# LTEMSubsystem.net
KiCad netlist of a schematic drawn in Altium Designer
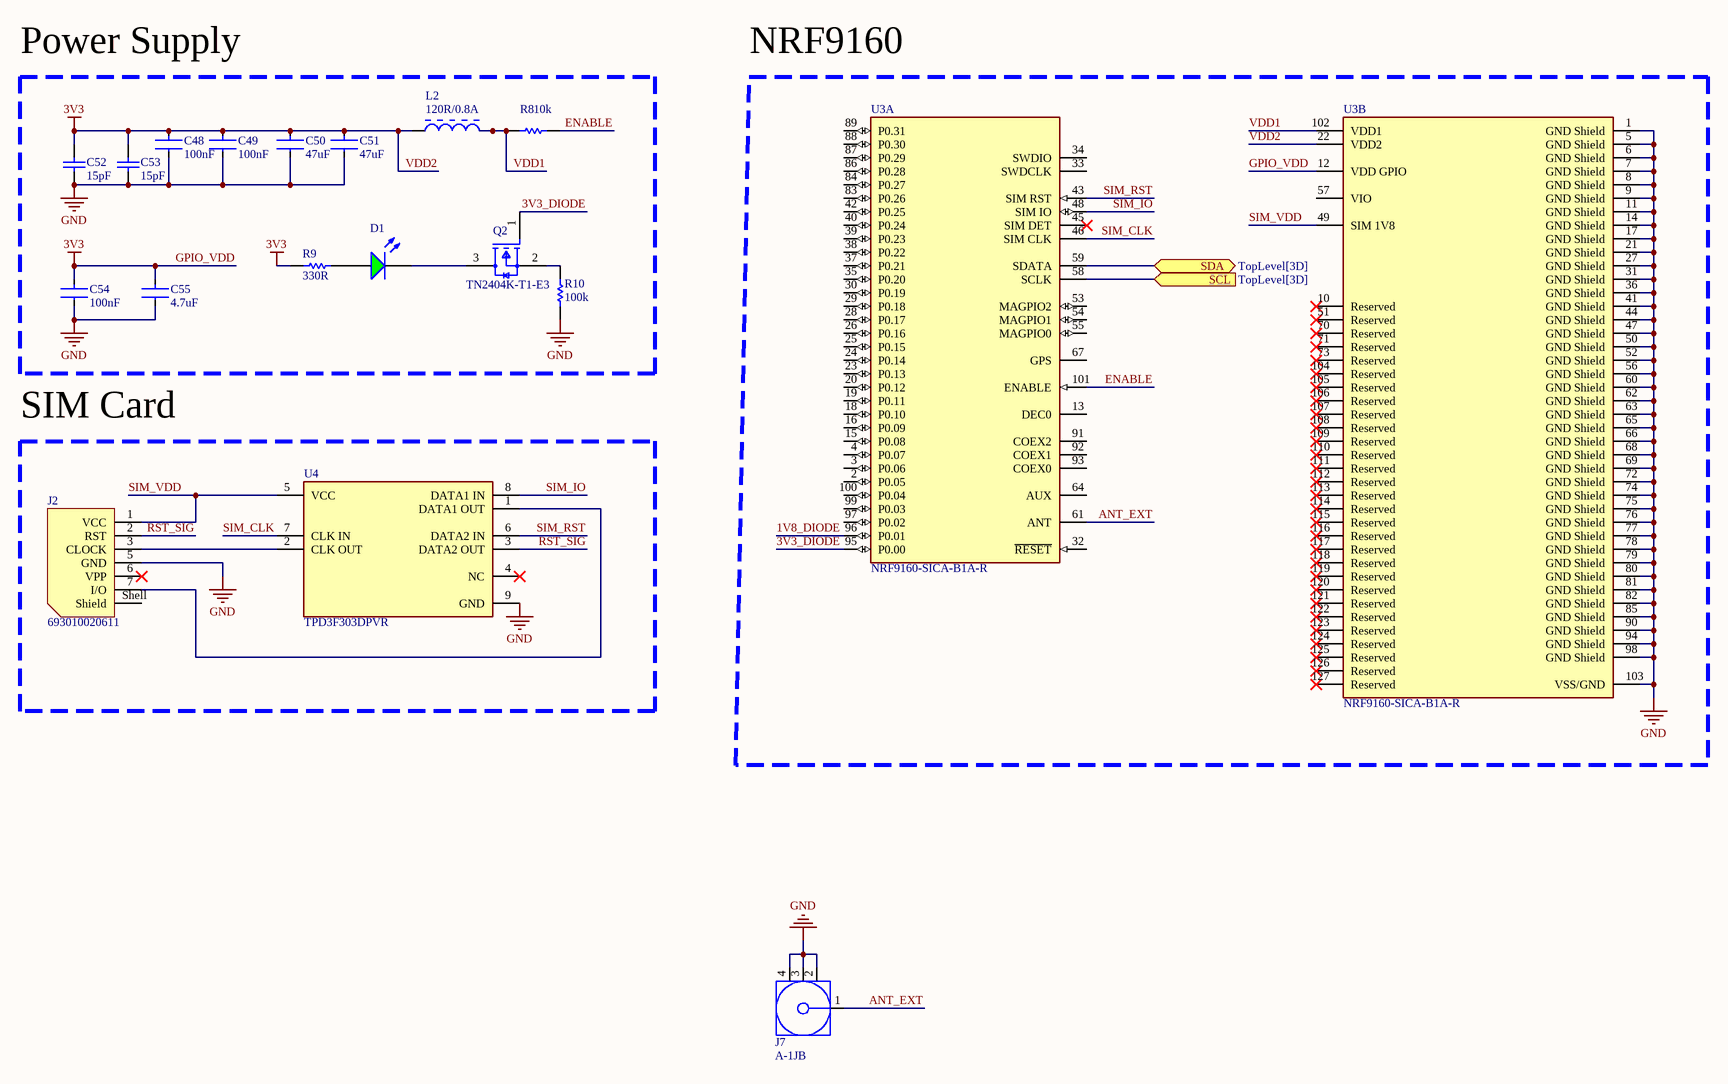
[diagram p0: LTEMSubsystem.SchDoc]

(export (version "E")
  (design (tool "Eeschema 10.0.6"))
  (components
    (comp (ref "C48")
      (value "100nF")
      (footprint "FP-GRM033-0_03-MFG")
      (description "GRM033R60J104KE19D")
      (fields (field (name "VOLTAGE") "6.3V") (field (name "TOLERANCE") "10%"))
      (libsource (lib "Altium Content Vault") (part "b4654b650e69147ec39a6b967a45e02"))
    )
    (comp (ref "C49")
      (value "100nF")
      (footprint "FP-GRM033-0_03-MFG")
      (description "GRM033R60J104KE19D")
      (fields (field (name "VOLTAGE") "6.3V") (field (name "TOLERANCE") "10%"))
      (libsource (lib "Altium Content Vault") (part "b4654b650e69147ec39a6b967a45e02"))
    )
    (comp (ref "C50")
      (value "47uF")
      (footprint "FP-C3216-160-0_2-MFG")
      (description "C3216X5R1C476M160AB")
      (fields (field (name "TOLERANCE") "20%"))
      (libsource (lib "Altium Content Vault") (part "11868f565c42a9108669ba33697ecf6"))
    )
    (comp (ref "C51")
      (value "47uF")
      (footprint "FP-C3216-160-0_2-MFG")
      (description "C3216X5R1C476M160AB")
      (fields (field (name "TOLERANCE") "20%"))
      (libsource (lib "Altium Content Vault") (part "11868f565c42a9108669ba33697ecf6"))
    )
    (comp (ref "C52")
      (value "15pF")
      (footprint "CAPC1508X91X25LL25T13")
      (description "06032U150GAT2A")
      (fields (field (name "MANUFACTURER") "AVX Interconnect / Elco"))
      (libsource (lib "Altium Content Vault") (part "CAP"))
    )
    (comp (ref "C53")
      (value "15pF")
      (footprint "CAPC1508X91X25LL25T13")
      (description "06032U150GAT2A")
      (fields (field (name "MANUFACTURER") "AVX Interconnect / Elco"))
      (libsource (lib "Altium Content Vault") (part "CAP"))
    )
    (comp (ref "C54")
      (value "100nF")
      (footprint "FP-GRM033-0_03-MFG")
      (description "GRM033R60J104KE19D")
      (fields (field (name "VOLTAGE") "6.3V") (field (name "TOLERANCE") "10%"))
      (libsource (lib "Altium Content Vault") (part "b4654b650e69147ec39a6b967a45e02"))
    )
    (comp (ref "C55")
      (value "4.7uF")
      (footprint "FP-C0603-CG-MFG")
      (description "C0603C475K9PACTU")
      (fields (field (name "TOLERANCE") "10%") (field (name "MANUFACTURER") "Kemet"))
      (libsource (lib "Altium Content Vault") (part "11868f565c42a9108669ba33697ecf6"))
    )
    (comp (ref "D1")
      (value "~")
      (footprint "WL-SMRW_1206_cylindrical_reverse use")
      (description "156120GS75300")
      (libsource (lib "Altium Content Vault") (part "LED_Green_2A-1K"))
    )
    (comp (ref "J2")
      (value "693010020611")
      (footprint "693010020611")
      (libsource (lib "Altium Content Vault") (part "693010020611"))
    )
    (comp (ref "J7")
      (value "A-1JB")
      (footprint "AMPH-A-1JB_V")
      (description "AMC PCB Jack, 0 to 60 GHz, 60 V, -40 to 90 degC, 4-Pin SMD, RoHS, Tape and Reel")
      (fields (field (name "TOLERANCE") "10%"))
      (libsource (lib "Altium Content Vault") (part "CN-S-3F-RF4"))
    )
    (comp (ref "L2")
      (value "120R/0.8A")
      (footprint "LIRD-LI0805H151R-10-2_V")
      (description "LI0805H121R-10")
      (fields (field (name "MANUFACTURER") "Laird"))
      (libsource (lib "Altium Content Vault") (part "IND-FB-2"))
    )
    (comp (ref "Q2")
      (value "TN2404K-T1-E3")
      (footprint "FP-S-03946-MFG")
      (description "TN2404K-T1-E3 Single N-Channel 240 V 4 Ohms Surface Mount Power Mosfet - SOT-23")
      (libsource (lib "Altium Content Vault") (part "0a9ea7c96deaaede766a5b531c28de0"))
    )
    (comp (ref "R8")
      (value "10k")
      (footprint "RESC1609X50X30NL8T20")
      (description "CRCW060310K0FKEA")
      (fields (field (name "MANUFACTURER") "Vishay Semiconductor"))
      (libsource (lib "Altium Content Vault") (part "RES-2"))
    )
    (comp (ref "R9")
      (value "330R")
      (footprint "RESC1005X40X25ML05T05")
      (description "ERJ2RKF3300X")
      (fields (field (name "MANUFACTURER") "Panasonic"))
      (libsource (lib "Altium Content Vault") (part "RES"))
    )
    (comp (ref "R10")
      (value "100k")
      (footprint "RESC1005X40X25NL10T10")
      (description "ERA-2AED104X")
      (fields (field (name "MANUFACTURER") "Panasonic"))
      (libsource (lib "Altium Content Vault") (part "RES"))
    )
    (comp (ref "U3")
      (value "NRF9160-SICA-B1A-R")
      (footprint "FP-NRF9160-SICA-B1A-R-MFG")
      (description "NRF9160-SICA-B1A-R LTE-M/NB-IoT/GPS Module 700MHz to 2200MHz 3.3V to 5.5V LGA")
      (libsource (lib "") (part "a84498b94899327ece239e71cba79b0_1"))
    )
    (comp (ref "U4")
      (value "TPD3F303DPVR")
      (footprint "FP-DPV0008A-IPC_C")
      (description "FILTER RC(PI) ESD SMD")
      (libsource (lib "Altium Content Vault") (part "1bc37876499b18a7cf6b6a3ecb1d701"))
    )
  )
  (nets
    (net (code "1") (name "/1V8_DIODE") (class "Default")
      (node (ref "U3") (pin "96") (pinfunction "P0.01_96") (pintype "bidirectional"))
    )
    (net (code "2") (name "/3V3_DIODE") (class "Default")
      (node (ref "Q2") (pin "1") (pinfunction "G_1") (pintype "passive"))
      (node (ref "U3") (pin "95") (pinfunction "P0.00_95") (pintype "bidirectional"))
    )
    (net (code "3") (name "/ANT_EXT") (class "Default")
      (node (ref "J7") (pin "1") (pinfunction "1_1") (pintype "passive"))
      (node (ref "U3") (pin "61") (pinfunction "ANT_61") (pintype "passive"))
    )
    (net (code "4") (name "/ENABLE") (class "Default")
      (node (ref "R8") (pin "2") (pinfunction "2_2") (pintype "passive"))
      (node (ref "U3") (pin "101") (pinfunction "ENABLE_101") (pintype "input"))
    )
    (net (code "5") (name "/RST_SIG") (class "Default")
      (node (ref "J2") (pin "2") (pinfunction "RST_2") (pintype "passive"))
      (node (ref "U4") (pin "3") (pinfunction "DATA2_OUT_3") (pintype "passive"))
    )
    (net (code "6") (name "/SCL") (class "Default")
      (node (ref "U3") (pin "58") (pinfunction "SCLK_58") (pintype "passive"))
    )
    (net (code "7") (name "/SDA") (class "Default")
      (node (ref "U3") (pin "59") (pinfunction "SDATA_59") (pintype "passive"))
    )
    (net (code "8") (name "/SIM_CLK") (class "Default")
      (node (ref "U3") (pin "46") (pinfunction "SIM_CLK_46") (pintype "passive"))
      (node (ref "U4") (pin "7") (pinfunction "CLK_IN_7") (pintype "passive"))
    )
    (net (code "9") (name "/SIM_IO") (class "Default")
      (node (ref "U3") (pin "48") (pinfunction "SIM_IO_48") (pintype "bidirectional"))
      (node (ref "U4") (pin "8") (pinfunction "DATA1_IN_8") (pintype "passive"))
    )
    (net (code "10") (name "/SIM_RST") (class "Default")
      (node (ref "U3") (pin "43") (pinfunction "SIM_RST_43") (pintype "input"))
      (node (ref "U4") (pin "6") (pinfunction "DATA2_IN_6") (pintype "passive"))
    )
    (net (code "11") (name "/SIM_VDD") (class "Default")
      (node (ref "J2") (pin "1") (pinfunction "VCC_1") (pintype "passive"))
      (node (ref "U3") (pin "49") (pinfunction "SIM_1V8_49") (pintype "power_in"))
      (node (ref "U4") (pin "5") (pinfunction "VCC_5") (pintype "power_in"))
    )
    (net (code "12") (name "/VDD1") (class "Default")
      (node (ref "L2") (pin "2") (pinfunction "2_2") (pintype "passive"))
      (node (ref "R8") (pin "1") (pinfunction "1_1") (pintype "passive"))
      (node (ref "U3") (pin "102") (pinfunction "VDD1_102") (pintype "power_in"))
    )
    (net (code "13") (name "3V3") (class "Default")
      (node (ref "C48") (pin "1") (pinfunction "1_1") (pintype "passive"))
      (node (ref "C49") (pin "1") (pinfunction "1_1") (pintype "passive"))
      (node (ref "C50") (pin "1") (pinfunction "1_1") (pintype "passive"))
      (node (ref "C51") (pin "1") (pinfunction "1_1") (pintype "passive"))
      (node (ref "C52") (pin "2") (pinfunction "2_2") (pintype "passive"))
      (node (ref "C53") (pin "2") (pinfunction "2_2") (pintype "passive"))
      (node (ref "C54") (pin "1") (pinfunction "1_1") (pintype "passive"))
      (node (ref "C55") (pin "1") (pinfunction "1_1") (pintype "passive"))
      (node (ref "L2") (pin "1") (pinfunction "1_1") (pintype "passive"))
      (node (ref "R9") (pin "1") (pinfunction "1_1") (pintype "passive"))
      (node (ref "U3") (pin "12") (pinfunction "VDD_GPIO_12") (pintype "power_in"))
      (node (ref "U3") (pin "22") (pinfunction "VDD2_22") (pintype "power_in"))
    )
    (net (code "14") (name "GND") (class "Default")
      (node (ref "C48") (pin "2") (pinfunction "2_2") (pintype "passive"))
      (node (ref "C49") (pin "2") (pinfunction "2_2") (pintype "passive"))
      (node (ref "C50") (pin "2") (pinfunction "2_2") (pintype "passive"))
      (node (ref "C51") (pin "2") (pinfunction "2_2") (pintype "passive"))
      (node (ref "C52") (pin "1") (pinfunction "1_1") (pintype "passive"))
      (node (ref "C53") (pin "1") (pinfunction "1_1") (pintype "passive"))
      (node (ref "C54") (pin "2") (pinfunction "2_2") (pintype "passive"))
      (node (ref "C55") (pin "2") (pinfunction "2_2") (pintype "passive"))
      (node (ref "J2") (pin "5") (pinfunction "GND_5") (pintype "passive"))
      (node (ref "J7") (pin "2") (pinfunction "2_2") (pintype "passive"))
      (node (ref "J7") (pin "3") (pinfunction "3_3") (pintype "passive"))
      (node (ref "J7") (pin "4") (pinfunction "4_4") (pintype "passive"))
      (node (ref "R10") (pin "2") (pinfunction "2_2") (pintype "passive"))
      (node (ref "U3") (pin "1") (pinfunction "GND_Shield_1") (pintype "power_in"))
      (node (ref "U3") (pin "103") (pinfunction "VSS/GND_103") (pintype "power_in"))
      (node (ref "U3") (pin "11") (pinfunction "GND_Shield_11") (pintype "power_in"))
      (node (ref "U3") (pin "14") (pinfunction "GND_Shield_14") (pintype "power_in"))
      (node (ref "U3") (pin "17") (pinfunction "GND_Shield_17") (pintype "power_in"))
      (node (ref "U3") (pin "21") (pinfunction "GND_Shield_21") (pintype "power_in"))
      (node (ref "U3") (pin "27") (pinfunction "GND_Shield_27") (pintype "power_in"))
      (node (ref "U3") (pin "31") (pinfunction "GND_Shield_31") (pintype "power_in"))
      (node (ref "U3") (pin "36") (pinfunction "GND_Shield_36") (pintype "power_in"))
      (node (ref "U3") (pin "41") (pinfunction "GND_Shield_41") (pintype "power_in"))
      (node (ref "U3") (pin "44") (pinfunction "GND_Shield_44") (pintype "power_in"))
      (node (ref "U3") (pin "47") (pinfunction "GND_Shield_47") (pintype "power_in"))
      (node (ref "U3") (pin "5") (pinfunction "GND_Shield_5") (pintype "power_in"))
      (node (ref "U3") (pin "50") (pinfunction "GND_Shield_50") (pintype "power_in"))
      (node (ref "U3") (pin "52") (pinfunction "GND_Shield_52") (pintype "power_in"))
      (node (ref "U3") (pin "56") (pinfunction "GND_Shield_56") (pintype "power_in"))
      (node (ref "U3") (pin "6") (pinfunction "GND_Shield_6") (pintype "power_in"))
      (node (ref "U3") (pin "60") (pinfunction "GND_Shield_60") (pintype "power_in"))
      (node (ref "U3") (pin "62") (pinfunction "GND_Shield_62") (pintype "power_in"))
      (node (ref "U3") (pin "63") (pinfunction "GND_Shield_63") (pintype "power_in"))
      (node (ref "U3") (pin "65") (pinfunction "GND_Shield_65") (pintype "power_in"))
      (node (ref "U3") (pin "66") (pinfunction "GND_Shield_66") (pintype "power_in"))
      (node (ref "U3") (pin "68") (pinfunction "GND_Shield_68") (pintype "power_in"))
      (node (ref "U3") (pin "69") (pinfunction "GND_Shield_69") (pintype "power_in"))
      (node (ref "U3") (pin "7") (pinfunction "GND_Shield_7") (pintype "power_in"))
      (node (ref "U3") (pin "72") (pinfunction "GND_Shield_72") (pintype "power_in"))
      (node (ref "U3") (pin "74") (pinfunction "GND_Shield_74") (pintype "power_in"))
      (node (ref "U3") (pin "75") (pinfunction "GND_Shield_75") (pintype "power_in"))
      (node (ref "U3") (pin "76") (pinfunction "GND_Shield_76") (pintype "power_in"))
      (node (ref "U3") (pin "77") (pinfunction "GND_Shield_77") (pintype "power_in"))
      (node (ref "U3") (pin "78") (pinfunction "GND_Shield_78") (pintype "power_in"))
      (node (ref "U3") (pin "79") (pinfunction "GND_Shield_79") (pintype "power_in"))
      (node (ref "U3") (pin "8") (pinfunction "GND_Shield_8") (pintype "power_in"))
      (node (ref "U3") (pin "80") (pinfunction "GND_Shield_80") (pintype "power_in"))
      (node (ref "U3") (pin "81") (pinfunction "GND_Shield_81") (pintype "power_in"))
      (node (ref "U3") (pin "82") (pinfunction "GND_Shield_82") (pintype "power_in"))
      (node (ref "U3") (pin "85") (pinfunction "GND_Shield_85") (pintype "power_in"))
      (node (ref "U3") (pin "9") (pinfunction "GND_Shield_9") (pintype "power_in"))
      (node (ref "U3") (pin "90") (pinfunction "GND_Shield_90") (pintype "power_in"))
      (node (ref "U3") (pin "94") (pinfunction "GND_Shield_94") (pintype "power_in"))
      (node (ref "U3") (pin "98") (pinfunction "GND_Shield_98") (pintype "power_in"))
      (node (ref "U4") (pin "9") (pinfunction "GND_9") (pintype "power_in"))
    )
    (net (code "15") (name "Net-(D1-A)") (class "Default")
      (node (ref "D1") (pin "2") (pinfunction "A_2") (pintype "passive"))
      (node (ref "R9") (pin "2") (pinfunction "2_2") (pintype "passive"))
    )
    (net (code "16") (name "Net-(D1-K)") (class "Default")
      (node (ref "D1") (pin "1") (pinfunction "K_1") (pintype "passive"))
      (node (ref "Q2") (pin "3") (pinfunction "D_3") (pintype "passive"))
    )
    (net (code "17") (name "Net-(J2-CLOCK)") (class "Default")
      (node (ref "J2") (pin "3") (pinfunction "CLOCK_3") (pintype "passive"))
      (node (ref "U4") (pin "2") (pinfunction "CLK_OUT_2") (pintype "passive"))
    )
    (net (code "18") (name "Net-(J2-I{slash}O)") (class "Default")
      (node (ref "J2") (pin "7") (pinfunction "I/O_7") (pintype "passive"))
      (node (ref "U4") (pin "1") (pinfunction "DATA1_OUT_1") (pintype "passive"))
    )
    (net (code "19") (name "Net-(Q2-S)") (class "Default")
      (node (ref "Q2") (pin "2") (pinfunction "S_2") (pintype "passive"))
      (node (ref "R10") (pin "1") (pinfunction "1_1") (pintype "passive"))
    )
    (net (code "20") (name "unconnected-(J2-Shield-PadShell)") (class "Default")
      (node (ref "J2") (pin "Shell") (pinfunction "Shield_Shell") (pintype "passive"))
    )
    (net (code "21") (name "unconnected-(J2-VPP-Pad6)") (class "Default")
      (node (ref "J2") (pin "6") (pinfunction "VPP_6") (pintype "passive+no_connect"))
    )
    (net (code "22") (name "unconnected-(U3A-AUX-Pad64)") (class "Default")
      (node (ref "U3") (pin "64") (pinfunction "AUX_64") (pintype "passive"))
    )
    (net (code "23") (name "unconnected-(U3A-COEX0-Pad93)") (class "Default")
      (node (ref "U3") (pin "93") (pinfunction "COEX0_93") (pintype "passive"))
    )
    (net (code "24") (name "unconnected-(U3A-COEX1-Pad92)") (class "Default")
      (node (ref "U3") (pin "92") (pinfunction "COEX1_92") (pintype "passive"))
    )
    (net (code "25") (name "unconnected-(U3A-COEX2-Pad91)") (class "Default")
      (node (ref "U3") (pin "91") (pinfunction "COEX2_91") (pintype "passive"))
    )
    (net (code "26") (name "unconnected-(U3A-DEC0-Pad13)") (class "Default")
      (node (ref "U3") (pin "13") (pinfunction "DEC0_13") (pintype "passive"))
    )
    (net (code "27") (name "unconnected-(U3A-GPS-Pad67)") (class "Default")
      (node (ref "U3") (pin "67") (pinfunction "GPS_67") (pintype "passive"))
    )
    (net (code "28") (name "unconnected-(U3A-MAGPIO0-Pad55)") (class "Default")
      (node (ref "U3") (pin "55") (pinfunction "MAGPIO0_55") (pintype "bidirectional"))
    )
    (net (code "29") (name "unconnected-(U3A-MAGPIO1-Pad54)") (class "Default")
      (node (ref "U3") (pin "54") (pinfunction "MAGPIO1_54") (pintype "bidirectional"))
    )
    (net (code "30") (name "unconnected-(U3A-MAGPIO2-Pad53)") (class "Default")
      (node (ref "U3") (pin "53") (pinfunction "MAGPIO2_53") (pintype "bidirectional"))
    )
    (net (code "31") (name "unconnected-(U3A-P0.02-Pad97)") (class "Default")
      (node (ref "U3") (pin "97") (pinfunction "P0.02_97") (pintype "bidirectional"))
    )
    (net (code "32") (name "unconnected-(U3A-P0.03-Pad99)") (class "Default")
      (node (ref "U3") (pin "99") (pinfunction "P0.03_99") (pintype "bidirectional"))
    )
    (net (code "33") (name "unconnected-(U3A-P0.04-Pad100)") (class "Default")
      (node (ref "U3") (pin "100") (pinfunction "P0.04_100") (pintype "bidirectional"))
    )
    (net (code "34") (name "unconnected-(U3A-P0.05-Pad2)") (class "Default")
      (node (ref "U3") (pin "2") (pinfunction "P0.05_2") (pintype "bidirectional"))
    )
    (net (code "35") (name "unconnected-(U3A-P0.06-Pad3)") (class "Default")
      (node (ref "U3") (pin "3") (pinfunction "P0.06_3") (pintype "bidirectional"))
    )
    (net (code "36") (name "unconnected-(U3A-P0.07-Pad4)") (class "Default")
      (node (ref "U3") (pin "4") (pinfunction "P0.07_4") (pintype "bidirectional"))
    )
    (net (code "37") (name "unconnected-(U3A-P0.08-Pad15)") (class "Default")
      (node (ref "U3") (pin "15") (pinfunction "P0.08_15") (pintype "bidirectional"))
    )
    (net (code "38") (name "unconnected-(U3A-P0.09-Pad16)") (class "Default")
      (node (ref "U3") (pin "16") (pinfunction "P0.09_16") (pintype "bidirectional"))
    )
    (net (code "39") (name "unconnected-(U3A-P0.10-Pad18)") (class "Default")
      (node (ref "U3") (pin "18") (pinfunction "P0.10_18") (pintype "bidirectional"))
    )
    (net (code "40") (name "unconnected-(U3A-P0.11-Pad19)") (class "Default")
      (node (ref "U3") (pin "19") (pinfunction "P0.11_19") (pintype "bidirectional"))
    )
    (net (code "41") (name "unconnected-(U3A-P0.12-Pad20)") (class "Default")
      (node (ref "U3") (pin "20") (pinfunction "P0.12_20") (pintype "bidirectional"))
    )
    (net (code "42") (name "unconnected-(U3A-P0.13-Pad23)") (class "Default")
      (node (ref "U3") (pin "23") (pinfunction "P0.13_23") (pintype "bidirectional"))
    )
    (net (code "43") (name "unconnected-(U3A-P0.14-Pad24)") (class "Default")
      (node (ref "U3") (pin "24") (pinfunction "P0.14_24") (pintype "bidirectional"))
    )
    (net (code "44") (name "unconnected-(U3A-P0.15-Pad25)") (class "Default")
      (node (ref "U3") (pin "25") (pinfunction "P0.15_25") (pintype "bidirectional"))
    )
    (net (code "45") (name "unconnected-(U3A-P0.16-Pad26)") (class "Default")
      (node (ref "U3") (pin "26") (pinfunction "P0.16_26") (pintype "bidirectional"))
    )
    (net (code "46") (name "unconnected-(U3A-P0.17-Pad28)") (class "Default")
      (node (ref "U3") (pin "28") (pinfunction "P0.17_28") (pintype "bidirectional"))
    )
    (net (code "47") (name "unconnected-(U3A-P0.18-Pad29)") (class "Default")
      (node (ref "U3") (pin "29") (pinfunction "P0.18_29") (pintype "bidirectional"))
    )
    (net (code "48") (name "unconnected-(U3A-P0.19-Pad30)") (class "Default")
      (node (ref "U3") (pin "30") (pinfunction "P0.19_30") (pintype "bidirectional"))
    )
    (net (code "49") (name "unconnected-(U3A-P0.20-Pad35)") (class "Default")
      (node (ref "U3") (pin "35") (pinfunction "P0.20_35") (pintype "bidirectional"))
    )
    (net (code "50") (name "unconnected-(U3A-P0.21-Pad37)") (class "Default")
      (node (ref "U3") (pin "37") (pinfunction "P0.21_37") (pintype "bidirectional"))
    )
    (net (code "51") (name "unconnected-(U3A-P0.22-Pad38)") (class "Default")
      (node (ref "U3") (pin "38") (pinfunction "P0.22_38") (pintype "bidirectional"))
    )
    (net (code "52") (name "unconnected-(U3A-P0.23-Pad39)") (class "Default")
      (node (ref "U3") (pin "39") (pinfunction "P0.23_39") (pintype "bidirectional"))
    )
    (net (code "53") (name "unconnected-(U3A-P0.24-Pad40)") (class "Default")
      (node (ref "U3") (pin "40") (pinfunction "P0.24_40") (pintype "bidirectional"))
    )
    (net (code "54") (name "unconnected-(U3A-P0.25-Pad42)") (class "Default")
      (node (ref "U3") (pin "42") (pinfunction "P0.25_42") (pintype "bidirectional"))
    )
    (net (code "55") (name "unconnected-(U3A-P0.26-Pad83)") (class "Default")
      (node (ref "U3") (pin "83") (pinfunction "P0.26_83") (pintype "bidirectional"))
    )
    (net (code "56") (name "unconnected-(U3A-P0.27-Pad84)") (class "Default")
      (node (ref "U3") (pin "84") (pinfunction "P0.27_84") (pintype "bidirectional"))
    )
    (net (code "57") (name "unconnected-(U3A-P0.28-Pad86)") (class "Default")
      (node (ref "U3") (pin "86") (pinfunction "P0.28_86") (pintype "bidirectional"))
    )
    (net (code "58") (name "unconnected-(U3A-P0.29-Pad87)") (class "Default")
      (node (ref "U3") (pin "87") (pinfunction "P0.29_87") (pintype "bidirectional"))
    )
    (net (code "59") (name "unconnected-(U3A-P0.30-Pad88)") (class "Default")
      (node (ref "U3") (pin "88") (pinfunction "P0.30_88") (pintype "bidirectional"))
    )
    (net (code "60") (name "unconnected-(U3A-P0.31-Pad89)") (class "Default")
      (node (ref "U3") (pin "89") (pinfunction "P0.31_89") (pintype "bidirectional"))
    )
    (net (code "61") (name "unconnected-(U3A-SIM_DET-Pad45)") (class "Default")
      (node (ref "U3") (pin "45") (pinfunction "SIM_DET_45") (pintype "passive+no_connect"))
    )
    (net (code "62") (name "unconnected-(U3A-SWDCLK-Pad33)") (class "Default")
      (node (ref "U3") (pin "33") (pinfunction "SWDCLK_33") (pintype "passive"))
    )
    (net (code "63") (name "unconnected-(U3A-SWDIO-Pad34)") (class "Default")
      (node (ref "U3") (pin "34") (pinfunction "SWDIO_34") (pintype "passive"))
    )
    (net (code "64") (name "unconnected-(U3A-~{RESET}-Pad32)") (class "Default")
      (node (ref "U3") (pin "32") (pinfunction "~{RESET}_32") (pintype "input"))
    )
    (net (code "65") (name "unconnected-(U3B-Reserved-Pad10)") (class "Default")
      (node (ref "U3") (pin "10") (pinfunction "Reserved_10") (pintype "passive+no_connect"))
    )
    (net (code "66") (name "unconnected-(U3B-Reserved-Pad51)") (class "Default")
      (node (ref "U3") (pin "51") (pinfunction "Reserved_51") (pintype "passive+no_connect"))
    )
    (net (code "67") (name "unconnected-(U3B-Reserved-Pad70)") (class "Default")
      (node (ref "U3") (pin "70") (pinfunction "Reserved_70") (pintype "passive+no_connect"))
    )
    (net (code "68") (name "unconnected-(U3B-Reserved-Pad71)") (class "Default")
      (node (ref "U3") (pin "71") (pinfunction "Reserved_71") (pintype "passive+no_connect"))
    )
    (net (code "69") (name "unconnected-(U3B-Reserved-Pad73)") (class "Default")
      (node (ref "U3") (pin "73") (pinfunction "Reserved_73") (pintype "passive+no_connect"))
    )
    (net (code "70") (name "unconnected-(U3B-Reserved-Pad104)") (class "Default")
      (node (ref "U3") (pin "104") (pinfunction "Reserved_104") (pintype "passive+no_connect"))
    )
    (net (code "71") (name "unconnected-(U3B-Reserved-Pad105)") (class "Default")
      (node (ref "U3") (pin "105") (pinfunction "Reserved_105") (pintype "passive+no_connect"))
    )
    (net (code "72") (name "unconnected-(U3B-Reserved-Pad106)") (class "Default")
      (node (ref "U3") (pin "106") (pinfunction "Reserved_106") (pintype "passive+no_connect"))
    )
    (net (code "73") (name "unconnected-(U3B-Reserved-Pad107)") (class "Default")
      (node (ref "U3") (pin "107") (pinfunction "Reserved_107") (pintype "passive+no_connect"))
    )
    (net (code "74") (name "unconnected-(U3B-Reserved-Pad108)") (class "Default")
      (node (ref "U3") (pin "108") (pinfunction "Reserved_108") (pintype "passive+no_connect"))
    )
    (net (code "75") (name "unconnected-(U3B-Reserved-Pad109)") (class "Default")
      (node (ref "U3") (pin "109") (pinfunction "Reserved_109") (pintype "passive+no_connect"))
    )
    (net (code "76") (name "unconnected-(U3B-Reserved-Pad110)") (class "Default")
      (node (ref "U3") (pin "110") (pinfunction "Reserved_110") (pintype "passive+no_connect"))
    )
    (net (code "77") (name "unconnected-(U3B-Reserved-Pad111)") (class "Default")
      (node (ref "U3") (pin "111") (pinfunction "Reserved_111") (pintype "passive+no_connect"))
    )
    (net (code "78") (name "unconnected-(U3B-Reserved-Pad112)") (class "Default")
      (node (ref "U3") (pin "112") (pinfunction "Reserved_112") (pintype "passive+no_connect"))
    )
    (net (code "79") (name "unconnected-(U3B-Reserved-Pad113)") (class "Default")
      (node (ref "U3") (pin "113") (pinfunction "Reserved_113") (pintype "passive+no_connect"))
    )
    (net (code "80") (name "unconnected-(U3B-Reserved-Pad114)") (class "Default")
      (node (ref "U3") (pin "114") (pinfunction "Reserved_114") (pintype "passive+no_connect"))
    )
    (net (code "81") (name "unconnected-(U3B-Reserved-Pad115)") (class "Default")
      (node (ref "U3") (pin "115") (pinfunction "Reserved_115") (pintype "passive+no_connect"))
    )
    (net (code "82") (name "unconnected-(U3B-Reserved-Pad116)") (class "Default")
      (node (ref "U3") (pin "116") (pinfunction "Reserved_116") (pintype "passive+no_connect"))
    )
    (net (code "83") (name "unconnected-(U3B-Reserved-Pad117)") (class "Default")
      (node (ref "U3") (pin "117") (pinfunction "Reserved_117") (pintype "passive+no_connect"))
    )
    (net (code "84") (name "unconnected-(U3B-Reserved-Pad118)") (class "Default")
      (node (ref "U3") (pin "118") (pinfunction "Reserved_118") (pintype "passive+no_connect"))
    )
    (net (code "85") (name "unconnected-(U3B-Reserved-Pad119)") (class "Default")
      (node (ref "U3") (pin "119") (pinfunction "Reserved_119") (pintype "passive+no_connect"))
    )
    (net (code "86") (name "unconnected-(U3B-Reserved-Pad120)") (class "Default")
      (node (ref "U3") (pin "120") (pinfunction "Reserved_120") (pintype "passive+no_connect"))
    )
    (net (code "87") (name "unconnected-(U3B-Reserved-Pad121)") (class "Default")
      (node (ref "U3") (pin "121") (pinfunction "Reserved_121") (pintype "passive+no_connect"))
    )
    (net (code "88") (name "unconnected-(U3B-Reserved-Pad122)") (class "Default")
      (node (ref "U3") (pin "122") (pinfunction "Reserved_122") (pintype "passive+no_connect"))
    )
    (net (code "89") (name "unconnected-(U3B-Reserved-Pad123)") (class "Default")
      (node (ref "U3") (pin "123") (pinfunction "Reserved_123") (pintype "passive+no_connect"))
    )
    (net (code "90") (name "unconnected-(U3B-Reserved-Pad124)") (class "Default")
      (node (ref "U3") (pin "124") (pinfunction "Reserved_124") (pintype "passive+no_connect"))
    )
    (net (code "91") (name "unconnected-(U3B-Reserved-Pad125)") (class "Default")
      (node (ref "U3") (pin "125") (pinfunction "Reserved_125") (pintype "passive+no_connect"))
    )
    (net (code "92") (name "unconnected-(U3B-Reserved-Pad126)") (class "Default")
      (node (ref "U3") (pin "126") (pinfunction "Reserved_126") (pintype "passive+no_connect"))
    )
    (net (code "93") (name "unconnected-(U3B-Reserved-Pad127)") (class "Default")
      (node (ref "U3") (pin "127") (pinfunction "Reserved_127") (pintype "passive+no_connect"))
    )
    (net (code "94") (name "unconnected-(U3B-VIO-Pad57)") (class "Default")
      (node (ref "U3") (pin "57") (pinfunction "VIO_57") (pintype "power_in"))
    )
    (net (code "95") (name "unconnected-(U4-NC-Pad4)") (class "Default")
      (node (ref "U4") (pin "4") (pinfunction "NC_4") (pintype "passive+no_connect"))
    )
  )
)
